# atmega328Pruebas.net
KiCad netlist of a schematic drawn in EAGLE
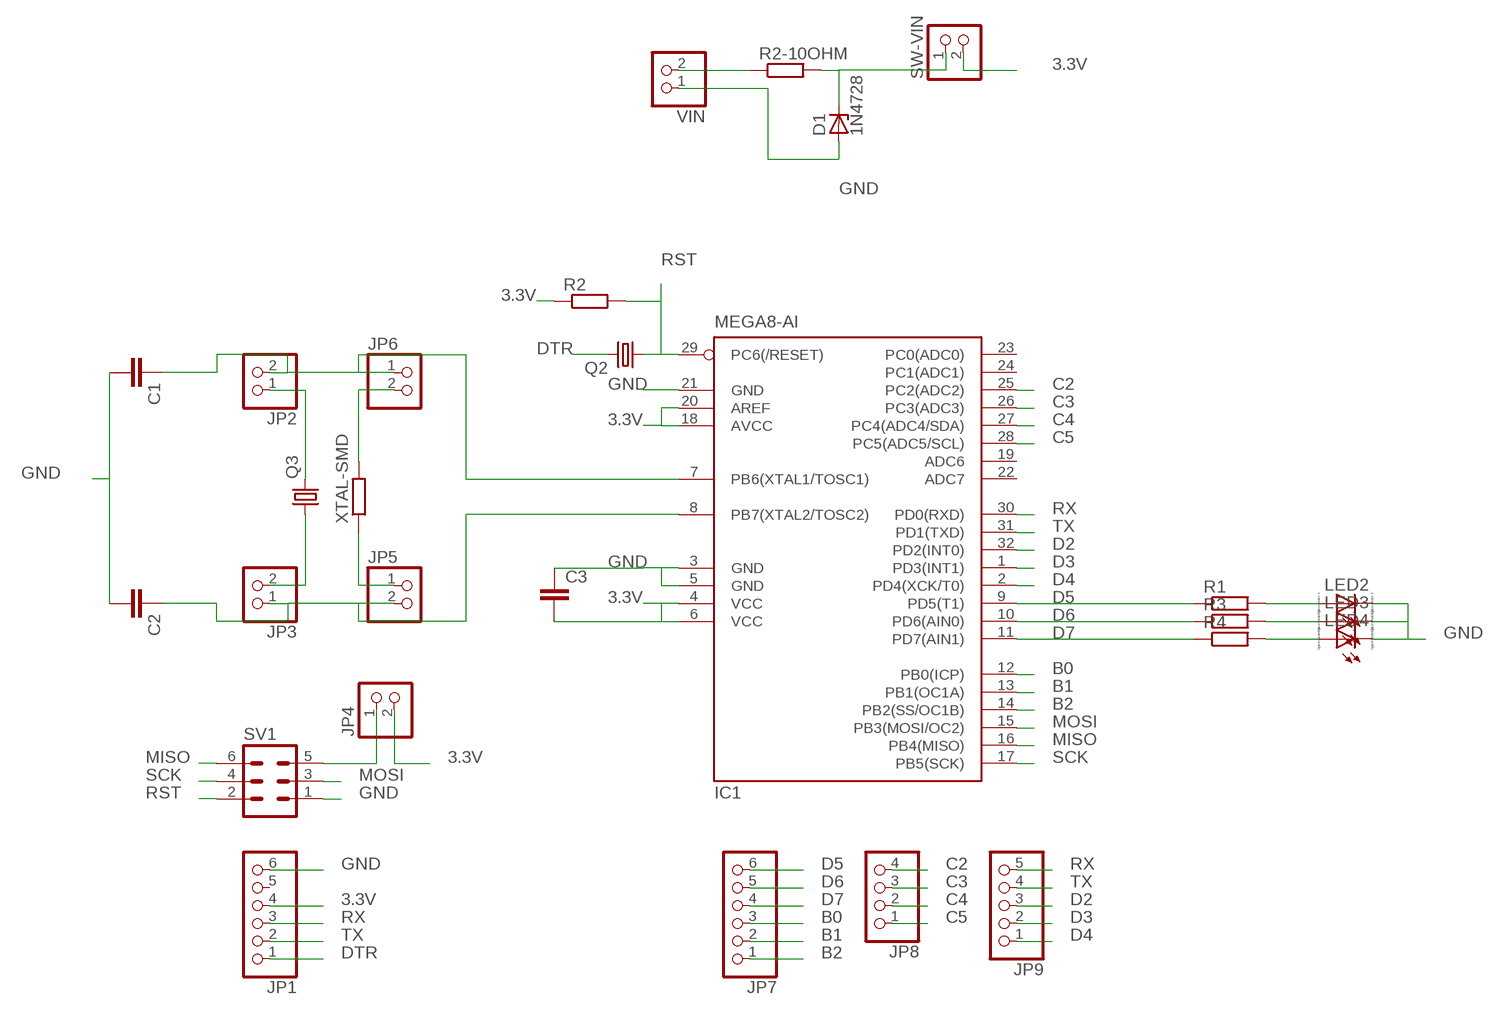
[diagram p0: schematic, sheet 1]

(export (version "E")
  (design (tool "Eeschema 10.0.6"))
  (components
    (comp (ref "C1")
      (value "C-EUC0402K")
      (footprint "eagle-import:C0402K")
      (libsource (lib "eagle-import") (part "C-EUC0402K"))
    )
    (comp (ref "C2")
      (value "C-EUC0402K")
      (footprint "eagle-import:C0402K")
      (libsource (lib "eagle-import") (part "C-EUC0402K"))
    )
    (comp (ref "C3")
      (value "C-EUC0402K")
      (footprint "eagle-import:C0402K")
      (libsource (lib "eagle-import") (part "C-EUC0402K"))
    )
    (comp (ref "D1")
      (value "1N4728")
      (footprint "eagle-import:DO41Z10")
      (libsource (lib "eagle-import") (part "1N4728"))
    )
    (comp (ref "IC1")
      (value "MEGA8-AI")
      (footprint "eagle-import:TQFP32-08")
      (fields (field (name "MPN") "ATMEGA8-16AU"))
      (libsource (lib "eagle-import") (part "MEGA8-AI"))
    )
    (comp (ref "JP1")
      (value "PINHD-1X6")
      (footprint "eagle-import:1X06")
      (libsource (lib "eagle-import") (part "PINHD-1X6"))
    )
    (comp (ref "JP2")
      (value "PINHD-1X2")
      (footprint "eagle-import:1X02")
      (libsource (lib "eagle-import") (part "PINHD-1X2"))
    )
    (comp (ref "JP3")
      (value "PINHD-1X2")
      (footprint "eagle-import:1X02")
      (libsource (lib "eagle-import") (part "PINHD-1X2"))
    )
    (comp (ref "JP4")
      (value "PINHD-1X2")
      (footprint "eagle-import:1X02")
      (libsource (lib "eagle-import") (part "PINHD-1X2"))
    )
    (comp (ref "JP5")
      (value "PINHD-1X2")
      (footprint "eagle-import:1X02")
      (libsource (lib "eagle-import") (part "PINHD-1X2"))
    )
    (comp (ref "JP6")
      (value "PINHD-1X2")
      (footprint "eagle-import:1X02")
      (libsource (lib "eagle-import") (part "PINHD-1X2"))
    )
    (comp (ref "JP7")
      (value "PINHD-1X6")
      (footprint "eagle-import:1X06")
      (libsource (lib "eagle-import") (part "PINHD-1X6"))
    )
    (comp (ref "JP8")
      (value "PINHD-1X4")
      (footprint "eagle-import:1X04")
      (libsource (lib "eagle-import") (part "PINHD-1X4"))
    )
    (comp (ref "JP9")
      (value "PINHD-1X5")
      (footprint "eagle-import:1X05")
      (libsource (lib "eagle-import") (part "PINHD-1X5"))
    )
    (comp (ref "LED2")
      (value "LED_ESML0603")
      (footprint "eagle-import:LED_SML0603")
      (libsource (lib "eagle-import") (part "LED_ESML0603"))
    )
    (comp (ref "LED3")
      (value "LED_ESML0603")
      (footprint "eagle-import:LED_SML0603")
      (libsource (lib "eagle-import") (part "LED_ESML0603"))
    )
    (comp (ref "LED4")
      (value "LED_ESML0603")
      (footprint "eagle-import:LED_SML0603")
      (libsource (lib "eagle-import") (part "LED_ESML0603"))
    )
    (comp (ref "Q2")
      (value "CRYSTALHC49U70")
      (footprint "eagle-import:HC49U70")
      (libsource (lib "eagle-import") (part "CRYSTALHC49U70"))
    )
    (comp (ref "Q3")
      (value "CRYSTALHC49U70")
      (footprint "eagle-import:HC49U70")
      (libsource (lib "eagle-import") (part "CRYSTALHC49U70"))
    )
    (comp (ref "R1")
      (value "R-EU_R0603")
      (footprint "eagle-import:R0603")
      (libsource (lib "eagle-import") (part "R-EU_R0603"))
    )
    (comp (ref "R2")
      (value "R-EU_R0603")
      (footprint "eagle-import:R0603")
      (libsource (lib "eagle-import") (part "R-EU_R0603"))
    )
    (comp (ref "R2-10OHM")
      (value "R-EU_R2512")
      (footprint "eagle-import:R2512")
      (libsource (lib "eagle-import") (part "resistor_R-EU_R2512"))
    )
    (comp (ref "R3")
      (value "R-EU_R0603")
      (footprint "eagle-import:R0603")
      (libsource (lib "eagle-import") (part "R-EU_R0603"))
    )
    (comp (ref "R4")
      (value "R-EU_R0603")
      (footprint "eagle-import:R0603")
      (libsource (lib "eagle-import") (part "R-EU_R0603"))
    )
    (comp (ref "SV1")
      (value "MA03-2")
      (footprint "eagle-import:MA03-2")
      (libsource (lib "eagle-import") (part "MA03-2"))
    )
    (comp (ref "SW-VIN")
      (value "PINHD-1X2")
      (footprint "eagle-import:1X02")
      (libsource (lib "eagle-import") (part "PINHD-1X2"))
    )
    (comp (ref "VIN")
      (value "PINHD-1X2")
      (footprint "eagle-import:1X02")
      (libsource (lib "eagle-import") (part "PINHD-1X2"))
    )
    (comp (ref "XTAL-SMD")
      (value "R-EU_M1206")
      (footprint "eagle-import:M1206")
      (libsource (lib "eagle-import") (part "R-EU_M1206"))
    )
  )
  (nets
    (net (code "1") (name "/3.3V") (class "Default")
      (node (ref "C3") (pin "2") (pinfunction "2_2") (pintype "passive"))
      (node (ref "IC1") (pin "18") (pinfunction "AVCC_18") (pintype "power_in"))
      (node (ref "IC1") (pin "20") (pinfunction "AREF_20") (pintype "passive"))
      (node (ref "IC1") (pin "4") (pinfunction "VCC_4") (pintype "power_in"))
      (node (ref "IC1") (pin "6") (pinfunction "VCC_6") (pintype "power_in"))
      (node (ref "JP1") (pin "4") (pinfunction "4_4") (pintype "passive"))
      (node (ref "JP4") (pin "2") (pinfunction "2_2") (pintype "passive"))
      (node (ref "R2") (pin "1") (pinfunction "1_1") (pintype "passive"))
      (node (ref "SW-VIN") (pin "2") (pinfunction "2_2") (pintype "passive"))
    )
    (net (code "2") (name "/B0") (class "Default")
      (node (ref "IC1") (pin "12") (pinfunction "PB0(ICP)_12") (pintype "bidirectional"))
      (node (ref "JP7") (pin "3") (pinfunction "3_3") (pintype "passive"))
    )
    (net (code "3") (name "/B1") (class "Default")
      (node (ref "IC1") (pin "13") (pinfunction "PB1(OC1A)_13") (pintype "bidirectional"))
      (node (ref "JP7") (pin "2") (pinfunction "2_2") (pintype "passive"))
    )
    (net (code "4") (name "/B2") (class "Default")
      (node (ref "IC1") (pin "14") (pinfunction "PB2(SS/OC1B)_14") (pintype "bidirectional"))
      (node (ref "JP7") (pin "1") (pinfunction "1_1") (pintype "passive"))
    )
    (net (code "5") (name "/C2") (class "Default")
      (node (ref "IC1") (pin "25") (pinfunction "PC2(ADC2)_25") (pintype "bidirectional"))
      (node (ref "JP8") (pin "4") (pinfunction "4_4") (pintype "passive"))
    )
    (net (code "6") (name "/C3") (class "Default")
      (node (ref "IC1") (pin "26") (pinfunction "PC3(ADC3)_26") (pintype "bidirectional"))
      (node (ref "JP8") (pin "3") (pinfunction "3_3") (pintype "passive"))
    )
    (net (code "7") (name "/C4") (class "Default")
      (node (ref "IC1") (pin "27") (pinfunction "PC4(ADC4/SDA)_27") (pintype "bidirectional"))
      (node (ref "JP8") (pin "2") (pinfunction "2_2") (pintype "passive"))
    )
    (net (code "8") (name "/C5") (class "Default")
      (node (ref "IC1") (pin "28") (pinfunction "PC5(ADC5/SCL)_28") (pintype "bidirectional"))
      (node (ref "JP8") (pin "1") (pinfunction "1_1") (pintype "passive"))
    )
    (net (code "9") (name "/D2") (class "Default")
      (node (ref "IC1") (pin "32") (pinfunction "PD2(INT0)_32") (pintype "bidirectional"))
      (node (ref "JP9") (pin "3") (pinfunction "3_3") (pintype "passive"))
    )
    (net (code "10") (name "/D3") (class "Default")
      (node (ref "IC1") (pin "1") (pinfunction "PD3(INT1)_1") (pintype "bidirectional"))
      (node (ref "JP9") (pin "2") (pinfunction "2_2") (pintype "passive"))
    )
    (net (code "11") (name "/D4") (class "Default")
      (node (ref "IC1") (pin "2") (pinfunction "PD4(XCK/T0)_2") (pintype "bidirectional"))
      (node (ref "JP9") (pin "1") (pinfunction "1_1") (pintype "passive"))
    )
    (net (code "12") (name "/D5") (class "Default")
      (node (ref "IC1") (pin "9") (pinfunction "PD5(T1)_9") (pintype "bidirectional"))
      (node (ref "JP7") (pin "6") (pinfunction "6_6") (pintype "passive"))
      (node (ref "R1") (pin "1") (pinfunction "1_1") (pintype "passive"))
    )
    (net (code "13") (name "/D6") (class "Default")
      (node (ref "IC1") (pin "10") (pinfunction "PD6(AIN0)_10") (pintype "bidirectional"))
      (node (ref "JP7") (pin "5") (pinfunction "5_5") (pintype "passive"))
      (node (ref "R3") (pin "1") (pinfunction "1_1") (pintype "passive"))
    )
    (net (code "14") (name "/D7") (class "Default")
      (node (ref "IC1") (pin "11") (pinfunction "PD7(AIN1)_11") (pintype "bidirectional"))
      (node (ref "JP7") (pin "4") (pinfunction "4_4") (pintype "passive"))
      (node (ref "R4") (pin "1") (pinfunction "1_1") (pintype "passive"))
    )
    (net (code "15") (name "/DTR") (class "Default")
      (node (ref "JP1") (pin "1") (pinfunction "1_1") (pintype "passive"))
      (node (ref "Q2") (pin "2") (pinfunction "2_2") (pintype "passive"))
    )
    (net (code "16") (name "/GND") (class "Default")
      (node (ref "C1") (pin "2") (pinfunction "2_2") (pintype "passive"))
      (node (ref "C2") (pin "2") (pinfunction "2_2") (pintype "passive"))
      (node (ref "C3") (pin "1") (pinfunction "1_1") (pintype "passive"))
      (node (ref "D1") (pin "A") (pinfunction "A_A") (pintype "passive"))
      (node (ref "IC1") (pin "21") (pinfunction "GND_21") (pintype "power_in"))
      (node (ref "IC1") (pin "3") (pinfunction "GND_3") (pintype "power_in"))
      (node (ref "IC1") (pin "5") (pinfunction "GND_5") (pintype "power_in"))
      (node (ref "JP1") (pin "6") (pinfunction "6_6") (pintype "passive"))
      (node (ref "LED2") (pin "C") (pinfunction "C_C") (pintype "passive"))
      (node (ref "LED3") (pin "C") (pinfunction "C_C") (pintype "passive"))
      (node (ref "LED4") (pin "C") (pinfunction "C_C") (pintype "passive"))
      (node (ref "SV1") (pin "1") (pinfunction "1_1") (pintype "passive"))
      (node (ref "VIN") (pin "1") (pinfunction "1_1") (pintype "passive"))
    )
    (net (code "17") (name "/MISO") (class "Default")
      (node (ref "IC1") (pin "16") (pinfunction "PB4(MISO)_16") (pintype "bidirectional"))
      (node (ref "SV1") (pin "6") (pinfunction "6_6") (pintype "passive"))
    )
    (net (code "18") (name "/MOSI") (class "Default")
      (node (ref "IC1") (pin "15") (pinfunction "PB3(MOSI/OC2)_15") (pintype "bidirectional"))
      (node (ref "SV1") (pin "3") (pinfunction "3_3") (pintype "passive"))
    )
    (net (code "19") (name "/RST") (class "Default")
      (node (ref "IC1") (pin "29") (pinfunction "PC6(/RESET)_29") (pintype "bidirectional"))
      (node (ref "Q2") (pin "1") (pinfunction "1_1") (pintype "passive"))
      (node (ref "R2") (pin "2") (pinfunction "2_2") (pintype "passive"))
      (node (ref "SV1") (pin "2") (pinfunction "2_2") (pintype "passive"))
    )
    (net (code "20") (name "/RX") (class "Default")
      (node (ref "IC1") (pin "30") (pinfunction "PD0(RXD)_30") (pintype "bidirectional"))
      (node (ref "JP1") (pin "3") (pinfunction "3_3") (pintype "passive"))
      (node (ref "JP9") (pin "5") (pinfunction "5_5") (pintype "passive"))
    )
    (net (code "21") (name "/SCK") (class "Default")
      (node (ref "IC1") (pin "17") (pinfunction "PB5(SCK)_17") (pintype "bidirectional"))
      (node (ref "SV1") (pin "4") (pinfunction "4_4") (pintype "passive"))
    )
    (net (code "22") (name "/TX") (class "Default")
      (node (ref "IC1") (pin "31") (pinfunction "PD1(TXD)_31") (pintype "bidirectional"))
      (node (ref "JP1") (pin "2") (pinfunction "2_2") (pintype "passive"))
      (node (ref "JP9") (pin "4") (pinfunction "4_4") (pintype "passive"))
    )
    (net (code "23") (name "Net-(D1-PadC)") (class "Default")
      (node (ref "D1") (pin "C") (pinfunction "C_C") (pintype "passive"))
      (node (ref "R2-10OHM") (pin "2") (pinfunction "2_2") (pintype "passive"))
      (node (ref "SW-VIN") (pin "1") (pinfunction "1_1") (pintype "passive"))
    )
    (net (code "24") (name "Net-(IC1-PB6(XTAL1{slash}TOSC1))") (class "Default")
      (node (ref "C1") (pin "1") (pinfunction "1_1") (pintype "passive"))
      (node (ref "IC1") (pin "7") (pinfunction "PB6(XTAL1/TOSC1)_7") (pintype "bidirectional"))
      (node (ref "JP2") (pin "2") (pinfunction "2_2") (pintype "passive"))
      (node (ref "JP6") (pin "1") (pinfunction "1_1") (pintype "passive"))
    )
    (net (code "25") (name "Net-(IC1-PB7(XTAL2{slash}TOSC2))") (class "Default")
      (node (ref "C2") (pin "1") (pinfunction "1_1") (pintype "passive"))
      (node (ref "IC1") (pin "8") (pinfunction "PB7(XTAL2/TOSC2)_8") (pintype "bidirectional"))
      (node (ref "JP3") (pin "1") (pinfunction "1_1") (pintype "passive"))
      (node (ref "JP5") (pin "2") (pinfunction "2_2") (pintype "passive"))
    )
    (net (code "26") (name "Net-(JP2-Pad1)") (class "Default")
      (node (ref "JP2") (pin "1") (pinfunction "1_1") (pintype "passive"))
      (node (ref "Q3") (pin "2") (pinfunction "2_2") (pintype "passive"))
    )
    (net (code "27") (name "Net-(JP3-Pad2)") (class "Default")
      (node (ref "JP3") (pin "2") (pinfunction "2_2") (pintype "passive"))
      (node (ref "Q3") (pin "1") (pinfunction "1_1") (pintype "passive"))
    )
    (net (code "28") (name "Net-(JP4-Pad1)") (class "Default")
      (node (ref "JP4") (pin "1") (pinfunction "1_1") (pintype "passive"))
      (node (ref "SV1") (pin "5") (pinfunction "5_5") (pintype "passive"))
    )
    (net (code "29") (name "Net-(JP5-Pad1)") (class "Default")
      (node (ref "JP5") (pin "1") (pinfunction "1_1") (pintype "passive"))
      (node (ref "XTAL-SMD") (pin "1") (pinfunction "1_1") (pintype "passive"))
    )
    (net (code "30") (name "Net-(JP6-Pad2)") (class "Default")
      (node (ref "JP6") (pin "2") (pinfunction "2_2") (pintype "passive"))
      (node (ref "XTAL-SMD") (pin "2") (pinfunction "2_2") (pintype "passive"))
    )
    (net (code "31") (name "Net-(LED2-PadA)") (class "Default")
      (node (ref "LED2") (pin "A") (pinfunction "A_A") (pintype "passive"))
      (node (ref "R1") (pin "2") (pinfunction "2_2") (pintype "passive"))
    )
    (net (code "32") (name "Net-(LED3-PadA)") (class "Default")
      (node (ref "LED3") (pin "A") (pinfunction "A_A") (pintype "passive"))
      (node (ref "R3") (pin "2") (pinfunction "2_2") (pintype "passive"))
    )
    (net (code "33") (name "Net-(LED4-PadA)") (class "Default")
      (node (ref "LED4") (pin "A") (pinfunction "A_A") (pintype "passive"))
      (node (ref "R4") (pin "2") (pinfunction "2_2") (pintype "passive"))
    )
    (net (code "34") (name "Net-(R2-10OHM-Pad1)") (class "Default")
      (node (ref "R2-10OHM") (pin "1") (pinfunction "1_1") (pintype "passive"))
      (node (ref "VIN") (pin "2") (pinfunction "2_2") (pintype "passive"))
    )
    (net (code "35") (name "unconnected-(IC1-ADC6-Pad19)") (class "Default")
      (node (ref "IC1") (pin "19") (pinfunction "ADC6_19") (pintype "bidirectional"))
    )
    (net (code "36") (name "unconnected-(IC1-ADC7-Pad22)") (class "Default")
      (node (ref "IC1") (pin "22") (pinfunction "ADC7_22") (pintype "bidirectional"))
    )
    (net (code "37") (name "unconnected-(IC1-PC0(ADC0)-Pad23)") (class "Default")
      (node (ref "IC1") (pin "23") (pinfunction "PC0(ADC0)_23") (pintype "bidirectional"))
    )
    (net (code "38") (name "unconnected-(IC1-PC1(ADC1)-Pad24)") (class "Default")
      (node (ref "IC1") (pin "24") (pinfunction "PC1(ADC1)_24") (pintype "bidirectional"))
    )
    (net (code "39") (name "unconnected-(JP1-Pad5)") (class "Default")
      (node (ref "JP1") (pin "5") (pinfunction "5_5") (pintype "passive"))
    )
  )
)
